# kilafors_rev_B.net
KiCad netlist of a schematic drawn in EAGLE
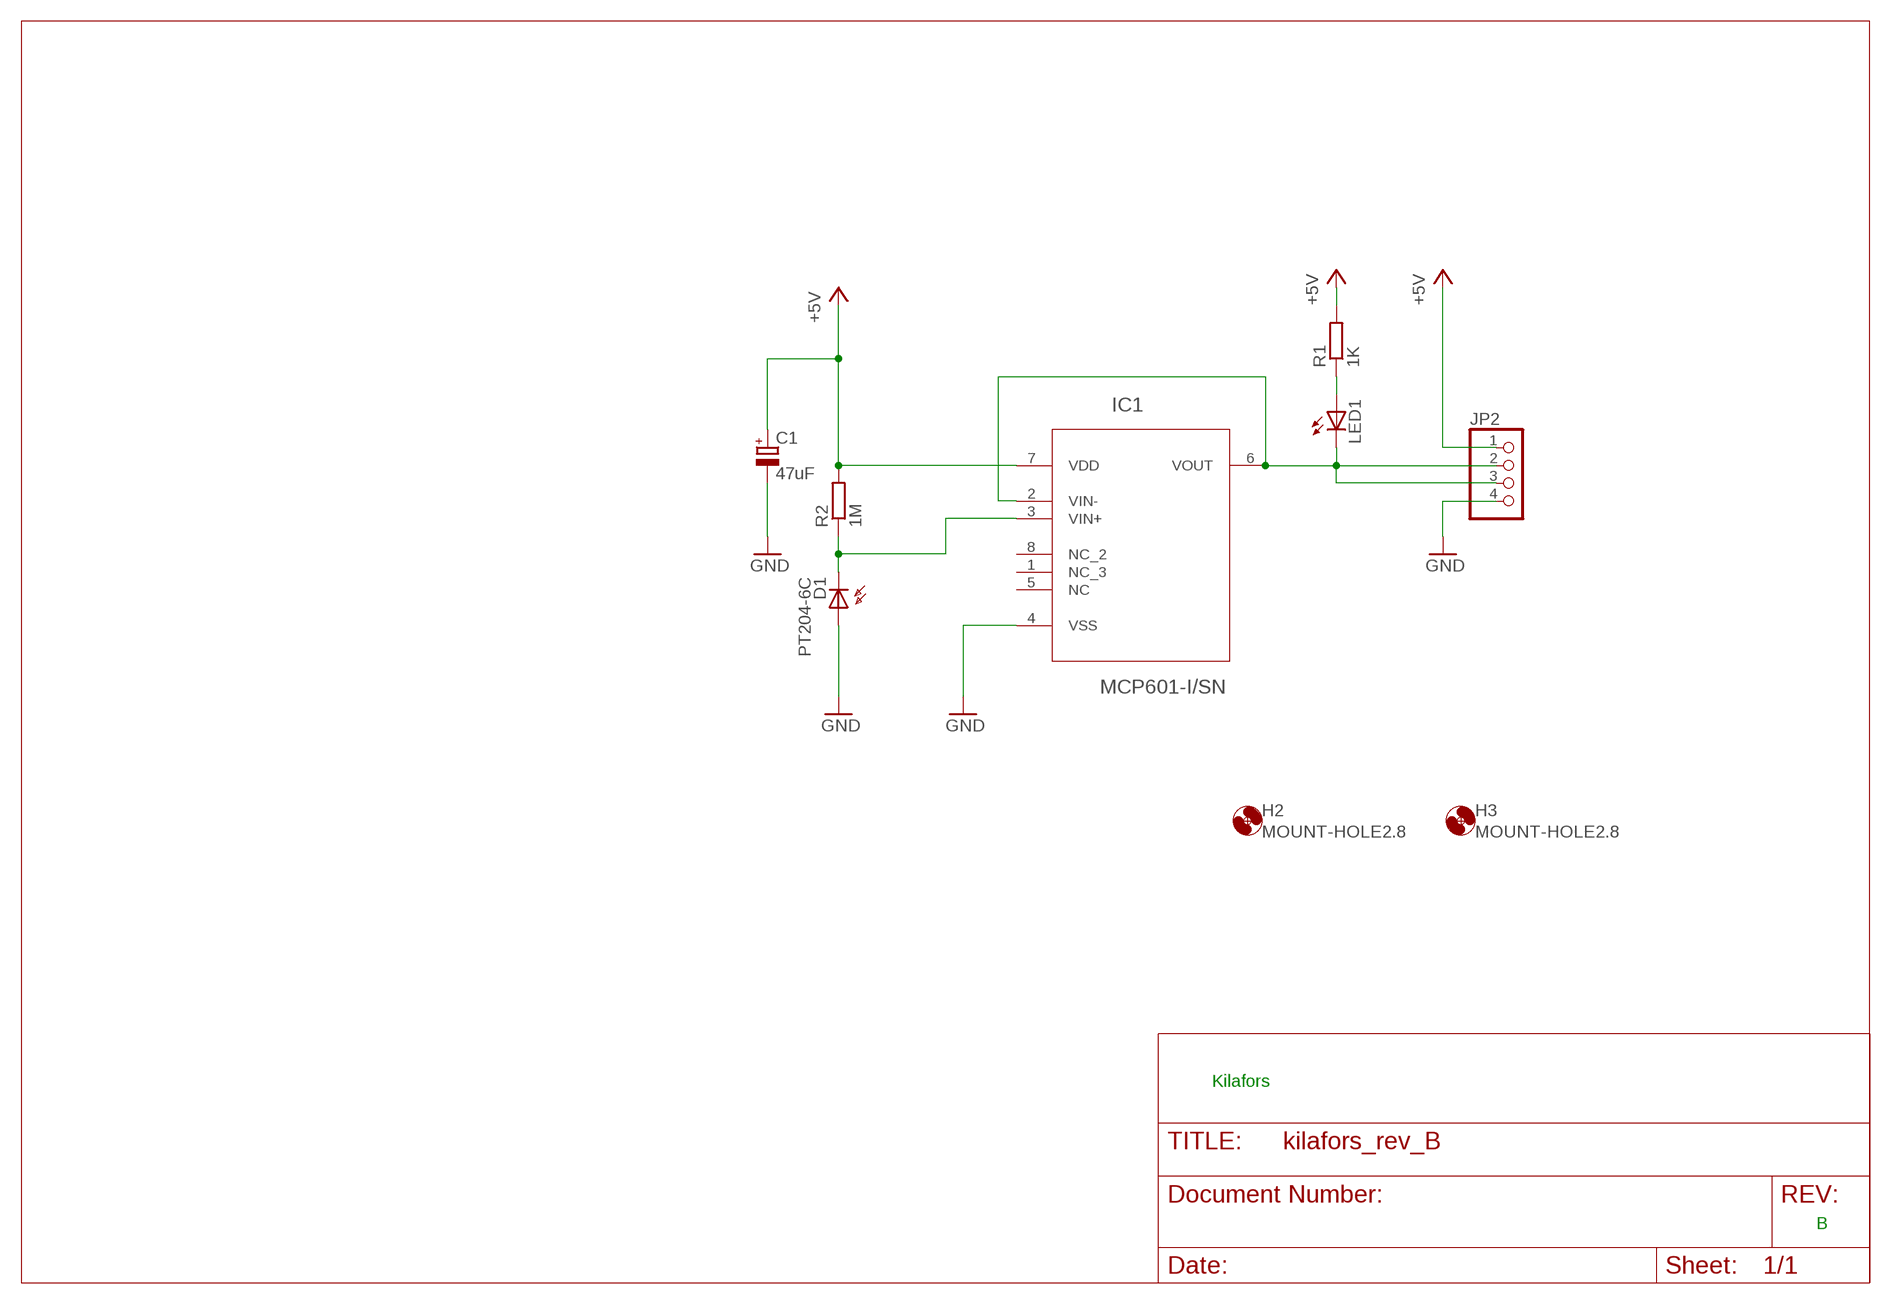
[diagram p0: schematic, sheet 1]

(export (version "E")
  (design (tool "Eeschema 10.0.6"))
  (components
    (comp (ref "C1")
      (value "47uF")
      (footprint "eagle-import:E5-5")
      (libsource (lib "eagle-import") (part "CPOL-EUE5-5"))
    )
    (comp (ref "D1")
      (value "PT204-6C")
      (footprint "eagle-import:BPW32")
      (libsource (lib "eagle-import") (part "BPW32"))
    )
    (comp (ref "H2")
      (value "MOUNT-HOLE2.8")
      (footprint "eagle-import:2,8")
      (libsource (lib "eagle-import") (part "MOUNT-HOLE2.8"))
    )
    (comp (ref "H3")
      (value "MOUNT-HOLE2.8")
      (footprint "eagle-import:2,8")
      (libsource (lib "eagle-import") (part "MOUNT-HOLE2.8"))
    )
    (comp (ref "IC1")
      (value "MCP601-I/SN")
      (footprint "eagle-import:SOIC127P600X175-8N")
      (libsource (lib "eagle-import") (part "MCP601-I/SN"))
    )
    (comp (ref "JP2")
      (value "PINHD-1X4")
      (footprint "eagle-import:1X04")
      (libsource (lib "eagle-import") (part "PINHD-1X4"))
    )
    (comp (ref "LED1")
      (value "LED3MM")
      (footprint "eagle-import:LED3MM")
      (libsource (lib "eagle-import") (part "LED3MM"))
    )
    (comp (ref "R1")
      (value "1K")
      (footprint "eagle-import:0204_5")
      (libsource (lib "eagle-import") (part "R-EU_0204/5"))
    )
    (comp (ref "R2")
      (value "1M")
      (footprint "eagle-import:0204_5")
      (libsource (lib "eagle-import") (part "R-EU_0204/5"))
    )
  )
  (nets
    (net (code "1") (name "+5V") (class "Default")
      (node (ref "C1") (pin "+") (pinfunction "+_+") (pintype "passive"))
      (node (ref "IC1") (pin "7") (pinfunction "VDD_7") (pintype "power_in"))
      (node (ref "JP2") (pin "1") (pinfunction "1_1") (pintype "passive"))
      (node (ref "R1") (pin "2") (pinfunction "2_2") (pintype "passive"))
      (node (ref "R2") (pin "2") (pinfunction "2_2") (pintype "passive"))
    )
    (net (code "2") (name "GND") (class "Default")
      (node (ref "C1") (pin "-") (pinfunction "-_-") (pintype "passive"))
      (node (ref "D1") (pin "A") (pinfunction "A_A") (pintype "passive"))
      (node (ref "IC1") (pin "4") (pinfunction "VSS_4") (pintype "power_in"))
      (node (ref "JP2") (pin "4") (pinfunction "4_4") (pintype "passive"))
    )
    (net (code "3") (name "Net-(D1-C)") (class "Default")
      (node (ref "D1") (pin "K") (pinfunction "C_K") (pintype "passive"))
      (node (ref "IC1") (pin "3") (pinfunction "VIN+_3") (pintype "input"))
      (node (ref "R2") (pin "1") (pinfunction "1_1") (pintype "passive"))
    )
    (net (code "4") (name "Net-(IC1-VIN-)") (class "Default")
      (node (ref "IC1") (pin "2") (pinfunction "VIN-_2") (pintype "input"))
      (node (ref "IC1") (pin "6") (pinfunction "VOUT_6") (pintype "output"))
      (node (ref "JP2") (pin "2") (pinfunction "2_2") (pintype "passive"))
      (node (ref "JP2") (pin "3") (pinfunction "3_3") (pintype "passive"))
      (node (ref "LED1") (pin "K") (pinfunction "C_K") (pintype "passive"))
    )
    (net (code "5") (name "Net-(LED1-PadA)") (class "Default")
      (node (ref "LED1") (pin "A") (pinfunction "A_A") (pintype "passive"))
      (node (ref "R1") (pin "1") (pinfunction "1_1") (pintype "passive"))
    )
    (net (code "6") (name "unconnected-(IC1-NC-Pad5)") (class "Default")
      (node (ref "IC1") (pin "5") (pinfunction "NC_5") (pintype "no_connect"))
    )
    (net (code "7") (name "unconnected-(IC1-NC_2-Pad8)") (class "Default")
      (node (ref "IC1") (pin "8") (pinfunction "NC_2_8") (pintype "no_connect"))
    )
    (net (code "8") (name "unconnected-(IC1-NC_3-Pad1)") (class "Default")
      (node (ref "IC1") (pin "1") (pinfunction "NC_3_1") (pintype "no_connect"))
    )
  )
)
